# Helmet_Drop_V2_1.net
KiCad netlist of a schematic drawn in EAGLE
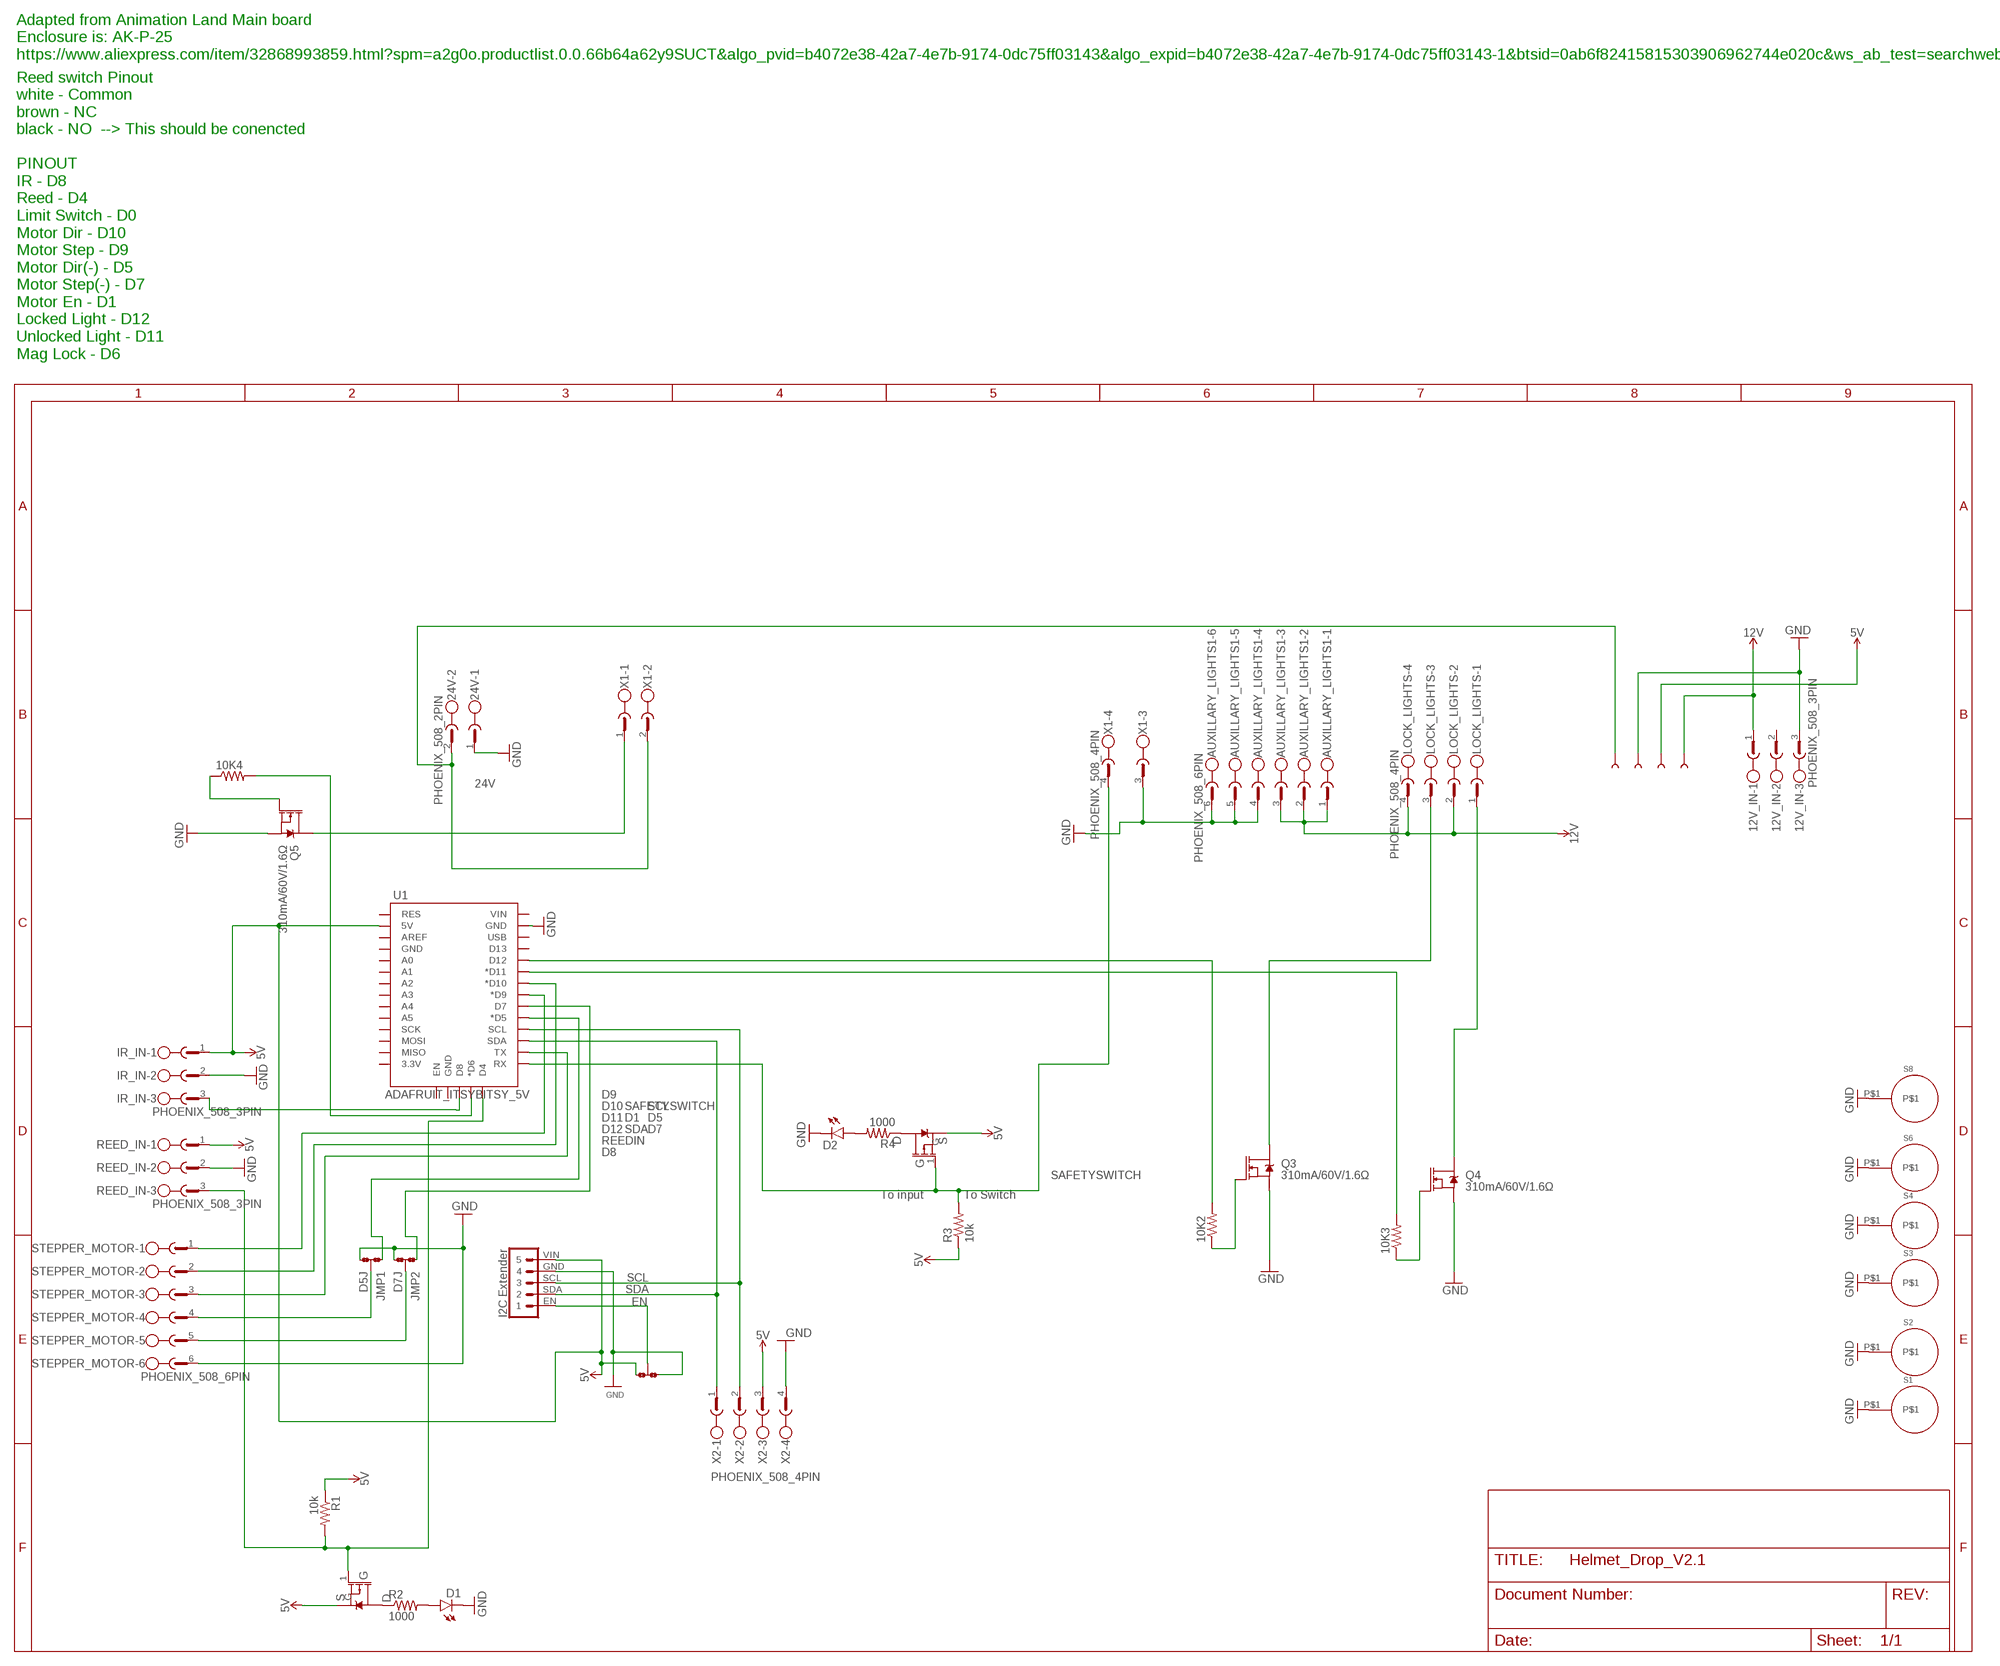
[diagram p0: schematic, sheet 1, part 1 of 2]
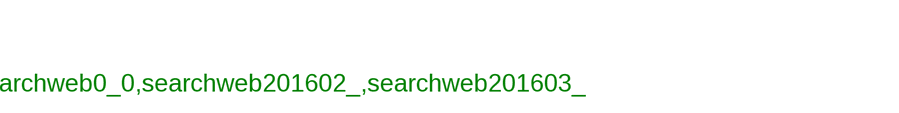
[diagram p1: schematic, sheet 1, part 2 of 2]

(export (version "E")
  (design (tool "Eeschema 10.0.6"))
  (components
    (comp (ref "10K2")
      (value "RESISTORS0805-RES")
      (footprint "eagle-import:SMD_RESISTOR_0805")
      (libsource (lib "eagle-import") (part "RESISTORS0805-RES"))
    )
    (comp (ref "10K3")
      (value "RESISTORS0805-RES")
      (footprint "eagle-import:SMD_RESISTOR_0805")
      (libsource (lib "eagle-import") (part "RESISTORS0805-RES"))
    )
    (comp (ref "10K4")
      (value "RESISTORS0805-RES")
      (footprint "eagle-import:SMD_RESISTOR_0805")
      (libsource (lib "eagle-import") (part "RESISTORS0805-RES"))
    )
    (comp (ref "12V_IN")
      (value "PHOENIX_508_3PIN")
      (footprint "eagle-import:PHOENIX_508_3PIN")
      (fields (field (name "MF") "FARNELL") (field (name "MPN") "1757255"))
      (libsource (lib "eagle-import") (part "PHOENIX_508_3PIN"))
    )
    (comp (ref "24V")
      (value "PHOENIX_508_2PIN")
      (footprint "eagle-import:PHOENIX_508_2PIN")
      (fields (field (name "MF") "FARNELL") (field (name "MPN") "1757242"))
      (libsource (lib "eagle-import") (part "PHOENIX_508_2PIN"))
    )
    (comp (ref "AUXILLARY_LIGHTS1")
      (value "PHOENIX_508_6PIN")
      (footprint "eagle-import:PHOENIX_508_6PIN")
      (fields (field (name "MF") "FARNELL") (field (name "MPN") "1757284"))
      (libsource (lib "eagle-import") (part "PHOENIX_508_6PIN"))
    )
    (comp (ref "D1")
      (value "GENERIC_LED1206")
      (footprint "eagle-import:SMD_LED-1206")
      (libsource (lib "eagle-import") (part "GENERIC_LED1206"))
    )
    (comp (ref "D2")
      (value "GENERIC_LED1206")
      (footprint "eagle-import:SMD_LED-1206")
      (libsource (lib "eagle-import") (part "GENERIC_LED1206"))
    )
    (comp (ref "IR_IN")
      (value "PHOENIX_508_3PIN")
      (footprint "eagle-import:PHOENIX_508_3PIN")
      (fields (field (name "MF") "FARNELL") (field (name "MPN") "1757255"))
      (libsource (lib "eagle-import") (part "PHOENIX_508_3PIN"))
    )
    (comp (ref "JMP1")
      (value "SMD_JUMPERA")
      (footprint "eagle-import:JUMPER_A-OR")
      (libsource (lib "eagle-import") (part "SMD_JUMPERA"))
    )
    (comp (ref "JMP2")
      (value "SMD_JUMPERA")
      (footprint "eagle-import:JUMPER_A-OR")
      (libsource (lib "eagle-import") (part "SMD_JUMPERA"))
    )
    (comp (ref "JMP3")
      (value "SMD_JUMPERA")
      (footprint "eagle-import:JUMPER_A-OR")
      (libsource (lib "eagle-import") (part "SMD_JUMPERA"))
    )
    (comp (ref "LOCK_LIGHTS")
      (value "PHOENIX_508_4PIN")
      (footprint "eagle-import:PHOENIX_508_4PIN")
      (fields (field (name "MF") "FARNELL") (field (name "MPN") "1757268"))
      (libsource (lib "eagle-import") (part "PHOENIX_508_4PIN"))
    )
    (comp (ref "Q1")
      (value "MOSFET-PCHIRLML9301TRPBF")
      (footprint "eagle-import:SOT23-3")
      (libsource (lib "eagle-import") (part "MOSFET-PCHIRLML9301TRPBF"))
    )
    (comp (ref "Q2")
      (value "MOSFET-PCHIRLML9301TRPBF")
      (footprint "eagle-import:SOT23-3")
      (libsource (lib "eagle-import") (part "MOSFET-PCHIRLML9301TRPBF"))
    )
    (comp (ref "Q3")
      (value "310mA/60V/1.6Ω")
      (footprint "eagle-import:SO-8_POWER_PAK")
      (libsource (lib "eagle-import") (part "MOSFET-NCH"))
    )
    (comp (ref "Q4")
      (value "310mA/60V/1.6Ω")
      (footprint "eagle-import:SO-8_POWER_PAK")
      (libsource (lib "eagle-import") (part "MOSFET-NCH"))
    )
    (comp (ref "Q5")
      (value "310mA/60V/1.6Ω")
      (footprint "eagle-import:SO-8_POWER_PAK")
      (libsource (lib "eagle-import") (part "MOSFET-NCH"))
    )
    (comp (ref "R1")
      (value "10k")
      (footprint "eagle-import:SMD_RESISTOR_0805")
      (libsource (lib "eagle-import") (part "RESISTORS0805-RES"))
    )
    (comp (ref "R2")
      (value "1000")
      (footprint "eagle-import:SMD_RESISTOR_0805")
      (libsource (lib "eagle-import") (part "RESISTORS0805-RES"))
    )
    (comp (ref "R3")
      (value "10k")
      (footprint "eagle-import:SMD_RESISTOR_0805")
      (libsource (lib "eagle-import") (part "RESISTORS0805-RES"))
    )
    (comp (ref "R4")
      (value "1000")
      (footprint "eagle-import:SMD_RESISTOR_0805")
      (libsource (lib "eagle-import") (part "RESISTORS0805-RES"))
    )
    (comp (ref "REED_IN")
      (value "PHOENIX_508_3PIN")
      (footprint "eagle-import:PHOENIX_508_3PIN")
      (fields (field (name "MF") "FARNELL") (field (name "MPN") "1757255"))
      (libsource (lib "eagle-import") (part "PHOENIX_508_3PIN"))
    )
    (comp (ref "S1")
      (value "GND_HOLE")
      (footprint "eagle-import:GND_HOLE")
      (libsource (lib "eagle-import") (part "GND_HOLE"))
    )
    (comp (ref "S2")
      (value "GND_HOLE")
      (footprint "eagle-import:GND_HOLE")
      (libsource (lib "eagle-import") (part "GND_HOLE"))
    )
    (comp (ref "S3")
      (value "GND_HOLE")
      (footprint "eagle-import:GND_HOLE")
      (libsource (lib "eagle-import") (part "GND_HOLE"))
    )
    (comp (ref "S4")
      (value "GND_HOLE")
      (footprint "eagle-import:GND_HOLE")
      (libsource (lib "eagle-import") (part "GND_HOLE"))
    )
    (comp (ref "S6")
      (value "GND_HOLE")
      (footprint "eagle-import:GND_HOLE")
      (libsource (lib "eagle-import") (part "GND_HOLE"))
    )
    (comp (ref "S8")
      (value "GND_HOLE")
      (footprint "eagle-import:GND_HOLE")
      (libsource (lib "eagle-import") (part "GND_HOLE"))
    )
    (comp (ref "STEPPER_MOTOR")
      (value "PHOENIX_508_6PIN")
      (footprint "eagle-import:PHOENIX_508_6PIN")
      (fields (field (name "MF") "FARNELL") (field (name "MPN") "1757284"))
      (libsource (lib "eagle-import") (part "PHOENIX_508_6PIN"))
    )
    (comp (ref "TP1")
      (value "TEST_POINTTP_15TH_THRU")
      (footprint "eagle-import:TESTPOINT_HEADER_1X01")
      (libsource (lib "eagle-import") (part "TEST_POINTTP_15TH_THRU"))
    )
    (comp (ref "TP2")
      (value "TEST_POINTTP_15TH_THRU")
      (footprint "eagle-import:TESTPOINT_HEADER_1X01")
      (libsource (lib "eagle-import") (part "TEST_POINTTP_15TH_THRU"))
    )
    (comp (ref "TP3")
      (value "TEST_POINTTP_15TH_THRU")
      (footprint "eagle-import:TESTPOINT_HEADER_1X01")
      (libsource (lib "eagle-import") (part "TEST_POINTTP_15TH_THRU"))
    )
    (comp (ref "TP4")
      (value "TEST_POINTTP_15TH_THRU")
      (footprint "eagle-import:TESTPOINT_HEADER_1X01")
      (libsource (lib "eagle-import") (part "TEST_POINTTP_15TH_THRU"))
    )
    (comp (ref "U$1")
      (value "I2C_EXTENDER")
      (footprint "eagle-import:I2C_EXTENDER")
      (libsource (lib "eagle-import") (part "I2C_EXTENDER"))
    )
    (comp (ref "U1")
      (value "ADAFRUIT_ITSYBITSY_5V")
      (footprint "eagle-import:ADAFRUIT_ITSYBITSY")
      (libsource (lib "eagle-import") (part "ADAFRUIT_ITSYBITSY_5V"))
    )
    (comp (ref "X1")
      (value "PHOENIX_508_4PIN")
      (footprint "eagle-import:PHOENIX_508_4PIN")
      (fields (field (name "MF") "FARNELL") (field (name "MPN") "1757268"))
      (libsource (lib "eagle-import") (part "PHOENIX_508_4PIN"))
    )
    (comp (ref "X2")
      (value "PHOENIX_508_4PIN")
      (footprint "eagle-import:PHOENIX_508_4PIN")
      (fields (field (name "MF") "FARNELL") (field (name "MPN") "1757268"))
      (libsource (lib "eagle-import") (part "PHOENIX_508_4PIN"))
    )
  )
  (nets
    (net (code "1") (name "/24V") (class "Default")
      (node (ref "24V") (pin "2") (pinfunction "1_2") (pintype "passive"))
      (node (ref "TP1") (pin "P$1") (pinfunction "1_P$1") (pintype "bidirectional"))
      (node (ref "X1") (pin "2") (pinfunction "1_2") (pintype "passive"))
    )
    (net (code "2") (name "/D1") (class "Default")
      (node (ref "STEPPER_MOTOR") (pin "3") (pinfunction "1_3") (pintype "passive"))
      (node (ref "U1") (pin "TX") (pinfunction "TX_TX") (pintype "bidirectional"))
    )
    (net (code "3") (name "/D5") (class "Default")
      (node (ref "JMP1") (pin "1") (pinfunction "1_1") (pintype "passive"))
      (node (ref "U1") (pin "D5") (pinfunction "*D5_D5") (pintype "bidirectional"))
    )
    (net (code "4") (name "/D5J") (class "Default")
      (node (ref "JMP1") (pin "2") (pinfunction "2_2") (pintype "passive"))
      (node (ref "STEPPER_MOTOR") (pin "4") (pinfunction "1_4") (pintype "passive"))
    )
    (net (code "5") (name "/D7") (class "Default")
      (node (ref "JMP2") (pin "1") (pinfunction "1_1") (pintype "passive"))
      (node (ref "U1") (pin "D7") (pinfunction "D7_D7") (pintype "bidirectional"))
    )
    (net (code "6") (name "/D7J") (class "Default")
      (node (ref "JMP2") (pin "2") (pinfunction "2_2") (pintype "passive"))
      (node (ref "STEPPER_MOTOR") (pin "5") (pinfunction "1_5") (pintype "passive"))
    )
    (net (code "7") (name "/D8") (class "Default")
      (node (ref "IR_IN") (pin "3") (pinfunction "1_3") (pintype "passive"))
      (node (ref "U1") (pin "D8") (pinfunction "D8_D8") (pintype "bidirectional"))
    )
    (net (code "8") (name "/D9") (class "Default")
      (node (ref "STEPPER_MOTOR") (pin "1") (pinfunction "1_1") (pintype "passive"))
      (node (ref "U1") (pin "D9") (pinfunction "*D9_D9") (pintype "bidirectional"))
    )
    (net (code "9") (name "/D10") (class "Default")
      (node (ref "STEPPER_MOTOR") (pin "2") (pinfunction "1_2") (pintype "passive"))
      (node (ref "U1") (pin "D10") (pinfunction "*D10_D10") (pintype "bidirectional"))
    )
    (net (code "10") (name "/D11") (class "Default")
      (node (ref "10K3") (pin "2") (pinfunction "2_2") (pintype "passive"))
      (node (ref "U1") (pin "D11") (pinfunction "*D11_D11") (pintype "bidirectional"))
    )
    (net (code "11") (name "/D12") (class "Default")
      (node (ref "10K2") (pin "2") (pinfunction "2_2") (pintype "passive"))
      (node (ref "U1") (pin "D12") (pinfunction "D12_D12") (pintype "bidirectional"))
    )
    (net (code "12") (name "/EN") (class "Default")
      (node (ref "JMP3") (pin "2") (pinfunction "2_2") (pintype "passive"))
      (node (ref "U$1") (pin "EN") (pinfunction "1_EN") (pintype "passive"))
    )
    (net (code "13") (name "/REEDIN") (class "Default")
      (node (ref "Q2") (pin "1") (pinfunction "G_1") (pintype "bidirectional"))
      (node (ref "R1") (pin "2") (pinfunction "2_2") (pintype "passive"))
      (node (ref "REED_IN") (pin "3") (pinfunction "1_3") (pintype "passive"))
      (node (ref "U1") (pin "D4") (pinfunction "D4_D4") (pintype "bidirectional"))
    )
    (net (code "14") (name "/SAFETYSWITCH") (class "Default")
      (node (ref "Q1") (pin "1") (pinfunction "G_1") (pintype "bidirectional"))
      (node (ref "R3") (pin "2") (pinfunction "2_2") (pintype "passive"))
      (node (ref "U1") (pin "RX") (pinfunction "RX_RX") (pintype "bidirectional"))
      (node (ref "X1") (pin "4") (pinfunction "1_4") (pintype "passive"))
    )
    (net (code "15") (name "/SCL") (class "Default")
      (node (ref "U$1") (pin "SCL") (pinfunction "3_SCL") (pintype "passive"))
      (node (ref "U1") (pin "SCL") (pinfunction "SCL_SCL") (pintype "bidirectional"))
      (node (ref "X2") (pin "2") (pinfunction "1_2") (pintype "passive"))
    )
    (net (code "16") (name "/SDA") (class "Default")
      (node (ref "U$1") (pin "SDA") (pinfunction "2_SDA") (pintype "passive"))
      (node (ref "U1") (pin "SDA") (pinfunction "SDA_SDA") (pintype "bidirectional"))
      (node (ref "X2") (pin "1") (pinfunction "1_1") (pintype "passive"))
    )
    (net (code "17") (name "5V") (class "Default")
      (node (ref "IR_IN") (pin "1") (pinfunction "1_1") (pintype "passive"))
      (node (ref "JMP3") (pin "1") (pinfunction "1_1") (pintype "passive"))
      (node (ref "Q1") (pin "2") (pinfunction "S_2") (pintype "bidirectional"))
      (node (ref "Q2") (pin "2") (pinfunction "S_2") (pintype "bidirectional"))
      (node (ref "R1") (pin "1") (pinfunction "1_1") (pintype "passive"))
      (node (ref "R3") (pin "1") (pinfunction "1_1") (pintype "passive"))
      (node (ref "REED_IN") (pin "1") (pinfunction "1_1") (pintype "passive"))
      (node (ref "TP3") (pin "P$1") (pinfunction "1_P$1") (pintype "bidirectional"))
      (node (ref "U$1") (pin "VIN") (pinfunction "5_VIN") (pintype "passive"))
      (node (ref "U1") (pin "5V") (pinfunction "5V_5V") (pintype "bidirectional"))
      (node (ref "X2") (pin "3") (pinfunction "1_3") (pintype "passive"))
    )
    (net (code "18") (name "12V") (class "Default")
      (node (ref "12V_IN") (pin "1") (pinfunction "1_1") (pintype "passive"))
      (node (ref "AUXILLARY_LIGHTS1") (pin "1") (pinfunction "1_1") (pintype "passive"))
      (node (ref "AUXILLARY_LIGHTS1") (pin "2") (pinfunction "1_2") (pintype "passive"))
      (node (ref "AUXILLARY_LIGHTS1") (pin "3") (pinfunction "1_3") (pintype "passive"))
      (node (ref "LOCK_LIGHTS") (pin "2") (pinfunction "1_2") (pintype "passive"))
      (node (ref "LOCK_LIGHTS") (pin "4") (pinfunction "1_4") (pintype "passive"))
      (node (ref "TP4") (pin "P$1") (pinfunction "1_P$1") (pintype "bidirectional"))
    )
    (net (code "19") (name "GND") (class "Default")
      (node (ref "12V_IN") (pin "3") (pinfunction "1_3") (pintype "passive"))
      (node (ref "24V") (pin "1") (pinfunction "1_1") (pintype "passive"))
      (node (ref "AUXILLARY_LIGHTS1") (pin "4") (pinfunction "1_4") (pintype "passive"))
      (node (ref "AUXILLARY_LIGHTS1") (pin "5") (pinfunction "1_5") (pintype "passive"))
      (node (ref "AUXILLARY_LIGHTS1") (pin "6") (pinfunction "1_6") (pintype "passive"))
      (node (ref "D1") (pin "C") (pinfunction "C_C") (pintype "passive"))
      (node (ref "D2") (pin "C") (pinfunction "C_C") (pintype "passive"))
      (node (ref "IR_IN") (pin "2") (pinfunction "1_2") (pintype "passive"))
      (node (ref "JMP1") (pin "3") (pinfunction "3_3") (pintype "passive"))
      (node (ref "JMP2") (pin "3") (pinfunction "3_3") (pintype "passive"))
      (node (ref "JMP3") (pin "3") (pinfunction "3_3") (pintype "passive"))
      (node (ref "Q3") (pin "S") (pinfunction "S_S") (pintype "bidirectional"))
      (node (ref "Q4") (pin "S") (pinfunction "S_S") (pintype "bidirectional"))
      (node (ref "Q5") (pin "S") (pinfunction "S_S") (pintype "bidirectional"))
      (node (ref "REED_IN") (pin "2") (pinfunction "1_2") (pintype "passive"))
      (node (ref "S1") (pin "P$1") (pinfunction "P$1_P$1") (pintype "bidirectional"))
      (node (ref "S2") (pin "P$1") (pinfunction "P$1_P$1") (pintype "bidirectional"))
      (node (ref "S3") (pin "P$1") (pinfunction "P$1_P$1") (pintype "bidirectional"))
      (node (ref "S4") (pin "P$1") (pinfunction "P$1_P$1") (pintype "bidirectional"))
      (node (ref "S6") (pin "P$1") (pinfunction "P$1_P$1") (pintype "bidirectional"))
      (node (ref "S8") (pin "P$1") (pinfunction "P$1_P$1") (pintype "bidirectional"))
      (node (ref "STEPPER_MOTOR") (pin "6") (pinfunction "1_6") (pintype "passive"))
      (node (ref "TP2") (pin "P$1") (pinfunction "1_P$1") (pintype "bidirectional"))
      (node (ref "U$1") (pin "GND") (pinfunction "4_GND") (pintype "passive"))
      (node (ref "U1") (pin "GND@2") (pinfunction "GND_GND@2") (pintype "bidirectional"))
      (node (ref "X1") (pin "3") (pinfunction "1_3") (pintype "passive"))
      (node (ref "X2") (pin "4") (pinfunction "1_4") (pintype "passive"))
    )
    (net (code "20") (name "Net-(10K2-Pad1)") (class "Default")
      (node (ref "10K2") (pin "1") (pinfunction "1_1") (pintype "passive"))
      (node (ref "Q3") (pin "G") (pinfunction "G_G") (pintype "bidirectional"))
    )
    (net (code "21") (name "Net-(10K3-Pad1)") (class "Default")
      (node (ref "10K3") (pin "1") (pinfunction "1_1") (pintype "passive"))
      (node (ref "Q4") (pin "G") (pinfunction "G_G") (pintype "bidirectional"))
    )
    (net (code "22") (name "Net-(10K4-Pad1)") (class "Default")
      (node (ref "10K4") (pin "1") (pinfunction "1_1") (pintype "passive"))
      (node (ref "Q5") (pin "G") (pinfunction "G_G") (pintype "bidirectional"))
    )
    (net (code "23") (name "Net-(D1-PadA)") (class "Default")
      (node (ref "D1") (pin "A") (pinfunction "A_A") (pintype "passive"))
      (node (ref "R2") (pin "2") (pinfunction "2_2") (pintype "passive"))
    )
    (net (code "24") (name "Net-(D2-PadA)") (class "Default")
      (node (ref "D2") (pin "A") (pinfunction "A_A") (pintype "passive"))
      (node (ref "R4") (pin "2") (pinfunction "2_2") (pintype "passive"))
    )
    (net (code "25") (name "Net-(LOCK_LIGHTSC-1)") (class "Default")
      (node (ref "LOCK_LIGHTS") (pin "3") (pinfunction "1_3") (pintype "passive"))
      (node (ref "Q3") (pin "D1") (pinfunction "D_D1") (pintype "bidirectional"))
    )
    (net (code "26") (name "Net-(Q1-D)") (class "Default")
      (node (ref "Q1") (pin "3") (pinfunction "D_3") (pintype "bidirectional"))
      (node (ref "R4") (pin "1") (pinfunction "1_1") (pintype "passive"))
    )
    (net (code "27") (name "Net-(Q2-D)") (class "Default")
      (node (ref "Q2") (pin "3") (pinfunction "D_3") (pintype "bidirectional"))
      (node (ref "R2") (pin "1") (pinfunction "1_1") (pintype "passive"))
    )
    (net (code "28") (name "Net-(Q4-D)") (class "Default")
      (node (ref "LOCK_LIGHTS") (pin "1") (pinfunction "1_1") (pintype "passive"))
      (node (ref "Q4") (pin "D1") (pinfunction "D_D1") (pintype "bidirectional"))
    )
    (net (code "29") (name "Net-(Q5-D)") (class "Default")
      (node (ref "Q5") (pin "D1") (pinfunction "D_D1") (pintype "bidirectional"))
      (node (ref "X1") (pin "1") (pinfunction "1_1") (pintype "passive"))
    )
    (net (code "30") (name "Net-(U1-*D6)") (class "Default")
      (node (ref "10K4") (pin "2") (pinfunction "2_2") (pintype "passive"))
      (node (ref "U1") (pin "D6") (pinfunction "*D6_D6") (pintype "bidirectional"))
    )
    (net (code "31") (name "unconnected-(12V_INB-1-Pad2)") (class "Default")
      (node (ref "12V_IN") (pin "2") (pinfunction "1_2") (pintype "passive"))
    )
    (net (code "32") (name "unconnected-(U1-3.3V-Pad3V)") (class "Default")
      (node (ref "U1") (pin "3V") (pinfunction "3.3V_3V") (pintype "bidirectional"))
    )
    (net (code "33") (name "unconnected-(U1-GND-PadGND@0)") (class "Default")
      (node (ref "U1") (pin "GND@0") (pinfunction "GND_GND@0") (pintype "bidirectional"))
    )
    (net (code "34") (name "unconnected-(U1-GND-PadGND@1)") (class "Default")
      (node (ref "U1") (pin "GND@1") (pinfunction "GND_GND@1") (pintype "bidirectional"))
    )
    (net (code "35") (name "unconnected-(U1-PadA0)") (class "Default")
      (node (ref "U1") (pin "A0") (pinfunction "A0_A0") (pintype "bidirectional"))
    )
    (net (code "36") (name "unconnected-(U1-PadA1)") (class "Default")
      (node (ref "U1") (pin "A1") (pinfunction "A1_A1") (pintype "bidirectional"))
    )
    (net (code "37") (name "unconnected-(U1-PadA2)") (class "Default")
      (node (ref "U1") (pin "A2") (pinfunction "A2_A2") (pintype "bidirectional"))
    )
    (net (code "38") (name "unconnected-(U1-PadA3)") (class "Default")
      (node (ref "U1") (pin "A3") (pinfunction "A3_A3") (pintype "bidirectional"))
    )
    (net (code "39") (name "unconnected-(U1-PadA4)") (class "Default")
      (node (ref "U1") (pin "A4") (pinfunction "A4_A4") (pintype "bidirectional"))
    )
    (net (code "40") (name "unconnected-(U1-PadA5)") (class "Default")
      (node (ref "U1") (pin "A5") (pinfunction "A5_A5") (pintype "bidirectional"))
    )
    (net (code "41") (name "unconnected-(U1-PadAREF)") (class "Default")
      (node (ref "U1") (pin "AREF") (pinfunction "AREF_AREF") (pintype "bidirectional"))
    )
    (net (code "42") (name "unconnected-(U1-PadD13)") (class "Default")
      (node (ref "U1") (pin "D13") (pinfunction "D13_D13") (pintype "bidirectional"))
    )
    (net (code "43") (name "unconnected-(U1-PadEN)") (class "Default")
      (node (ref "U1") (pin "EN") (pinfunction "EN_EN") (pintype "bidirectional"))
    )
    (net (code "44") (name "unconnected-(U1-PadMISO)") (class "Default")
      (node (ref "U1") (pin "MISO") (pinfunction "MISO_MISO") (pintype "bidirectional"))
    )
    (net (code "45") (name "unconnected-(U1-PadMOSI)") (class "Default")
      (node (ref "U1") (pin "MOSI") (pinfunction "MOSI_MOSI") (pintype "bidirectional"))
    )
    (net (code "46") (name "unconnected-(U1-PadRES)") (class "Default")
      (node (ref "U1") (pin "RES") (pinfunction "RES_RES") (pintype "bidirectional"))
    )
    (net (code "47") (name "unconnected-(U1-PadSCK)") (class "Default")
      (node (ref "U1") (pin "SCK") (pinfunction "SCK_SCK") (pintype "bidirectional"))
    )
    (net (code "48") (name "unconnected-(U1-PadUSB)") (class "Default")
      (node (ref "U1") (pin "USB") (pinfunction "USB_USB") (pintype "bidirectional"))
    )
    (net (code "49") (name "unconnected-(U1-PadVIN)") (class "Default")
      (node (ref "U1") (pin "VIN") (pinfunction "VIN_VIN") (pintype "bidirectional"))
    )
  )
)
